# untitled.net
KiCad netlist of a schematic drawn in EAGLE
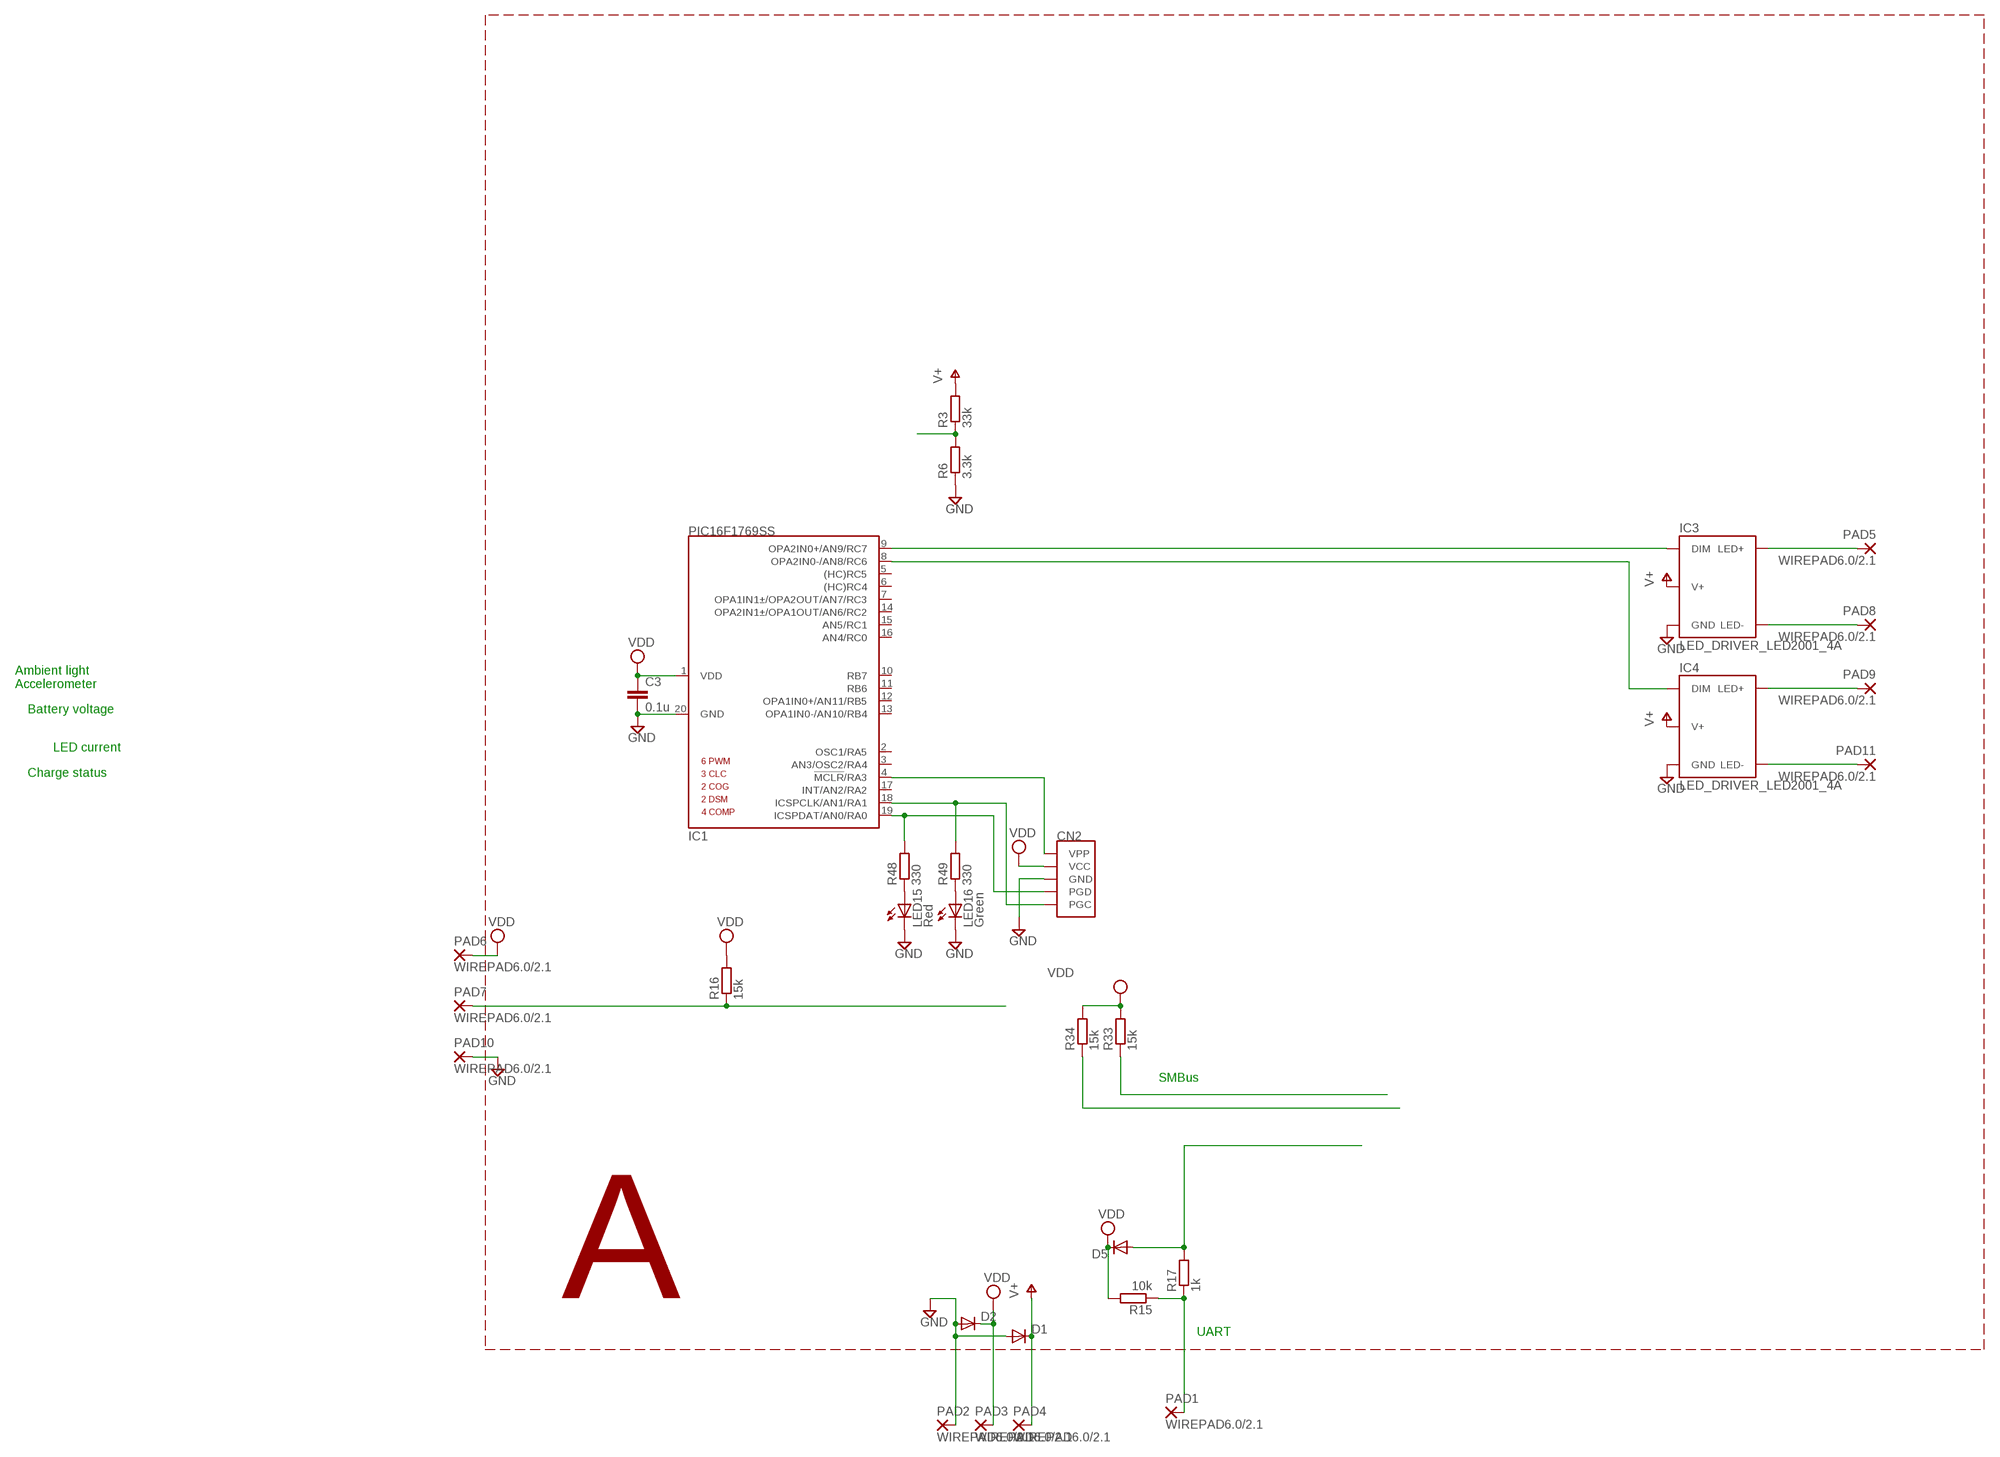
[diagram p0: schematic, sheet 1]

(export (version "E")
  (design (tool "Eeschema 10.0.6"))
  (components
    (comp (ref "C3")
      (value "0.1u")
      (footprint "eagle-import:C0402")
      (libsource (lib "eagle-import") (part "C-EUC0402"))
    )
    (comp (ref "CN2")
      (value "ICSPPIN")
      (footprint "eagle-import:MINI-ICSP_PIN")
      (libsource (lib "eagle-import") (part "ICSPPIN"))
    )
    (comp (ref "D1")
      (value "DIODE-VMN2")
      (footprint "eagle-import:VMN2")
      (libsource (lib "eagle-import") (part "DIODE-VMN2"))
    )
    (comp (ref "D2")
      (value "DIODE-VMN2")
      (footprint "eagle-import:VMN2")
      (libsource (lib "eagle-import") (part "DIODE-VMN2"))
    )
    (comp (ref "D5")
      (value "DIODE-VMN2")
      (footprint "eagle-import:VMN2")
      (libsource (lib "eagle-import") (part "DIODE-VMN2"))
    )
    (comp (ref "IC1")
      (value "PIC16F1769SS")
      (footprint "eagle-import:SSOP20")
      (libsource (lib "eagle-import") (part "PIC16F1769SS"))
    )
    (comp (ref "IC3")
      (value "LED_DRIVER_LED2001_4A")
      (footprint "eagle-import:LED_DRIVER_LED2001_4A")
      (libsource (lib "eagle-import") (part "LED_DRIVER_LED2001_4A"))
    )
    (comp (ref "IC4")
      (value "LED_DRIVER_LED2001_4A")
      (footprint "eagle-import:LED_DRIVER_LED2001_4A")
      (libsource (lib "eagle-import") (part "LED_DRIVER_LED2001_4A"))
    )
    (comp (ref "LED15")
      (value "Red")
      (footprint "eagle-import:LED3MM")
      (libsource (lib "eagle-import") (part "LED3MM"))
    )
    (comp (ref "LED16")
      (value "Green")
      (footprint "eagle-import:LED3MM")
      (libsource (lib "eagle-import") (part "LED3MM"))
    )
    (comp (ref "PAD1")
      (value "WIREPAD6.0/2.1")
      (footprint "eagle-import:6.0_2.1")
      (libsource (lib "eagle-import") (part "WIREPAD6.0/2.1"))
    )
    (comp (ref "PAD2")
      (value "WIREPAD6.0/2.1")
      (footprint "eagle-import:6.0_2.1")
      (libsource (lib "eagle-import") (part "WIREPAD6.0/2.1"))
    )
    (comp (ref "PAD3")
      (value "WIREPAD6.0/2.1")
      (footprint "eagle-import:6.0_2.1")
      (libsource (lib "eagle-import") (part "WIREPAD6.0/2.1"))
    )
    (comp (ref "PAD4")
      (value "WIREPAD6.0/2.1")
      (footprint "eagle-import:6.0_2.1")
      (libsource (lib "eagle-import") (part "WIREPAD6.0/2.1"))
    )
    (comp (ref "PAD5")
      (value "WIREPAD6.0/2.1")
      (footprint "eagle-import:6.0_2.1")
      (libsource (lib "eagle-import") (part "WIREPAD6.0/2.1"))
    )
    (comp (ref "PAD6")
      (value "WIREPAD6.0/2.1")
      (footprint "eagle-import:6.0_2.1")
      (libsource (lib "eagle-import") (part "WIREPAD6.0/2.1"))
    )
    (comp (ref "PAD7")
      (value "WIREPAD6.0/2.1")
      (footprint "eagle-import:6.0_2.1")
      (libsource (lib "eagle-import") (part "WIREPAD6.0/2.1"))
    )
    (comp (ref "PAD8")
      (value "WIREPAD6.0/2.1")
      (footprint "eagle-import:6.0_2.1")
      (libsource (lib "eagle-import") (part "WIREPAD6.0/2.1"))
    )
    (comp (ref "PAD9")
      (value "WIREPAD6.0/2.1")
      (footprint "eagle-import:6.0_2.1")
      (libsource (lib "eagle-import") (part "WIREPAD6.0/2.1"))
    )
    (comp (ref "PAD10")
      (value "WIREPAD6.0/2.1")
      (footprint "eagle-import:6.0_2.1")
      (libsource (lib "eagle-import") (part "WIREPAD6.0/2.1"))
    )
    (comp (ref "PAD11")
      (value "WIREPAD6.0/2.1")
      (footprint "eagle-import:6.0_2.1")
      (libsource (lib "eagle-import") (part "WIREPAD6.0/2.1"))
    )
    (comp (ref "R3")
      (value "33k")
      (footprint "eagle-import:R0402")
      (libsource (lib "eagle-import") (part "R-EU_R0402"))
    )
    (comp (ref "R6")
      (value "3.3k")
      (footprint "eagle-import:R0402")
      (libsource (lib "eagle-import") (part "R-EU_R0402"))
    )
    (comp (ref "R15")
      (value "10k")
      (footprint "eagle-import:R0402")
      (libsource (lib "eagle-import") (part "R-EU_R0402"))
    )
    (comp (ref "R16")
      (value "15k")
      (footprint "eagle-import:R0402")
      (libsource (lib "eagle-import") (part "R-EU_R0402"))
    )
    (comp (ref "R17")
      (value "1k")
      (footprint "eagle-import:R0402")
      (libsource (lib "eagle-import") (part "R-EU_R0402"))
    )
    (comp (ref "R33")
      (value "15k")
      (footprint "eagle-import:R0402")
      (libsource (lib "eagle-import") (part "R-EU_R0402"))
    )
    (comp (ref "R34")
      (value "15k")
      (footprint "eagle-import:R0402")
      (libsource (lib "eagle-import") (part "R-EU_R0402"))
    )
    (comp (ref "R48")
      (value "330")
      (footprint "eagle-import:R0402")
      (libsource (lib "eagle-import") (part "R-EU_R0402"))
    )
    (comp (ref "R49")
      (value "330")
      (footprint "eagle-import:R0402")
      (libsource (lib "eagle-import") (part "R-EU_R0402"))
    )
  )
  (nets
    (net (code "1") (name "GND") (class "Default")
      (node (ref "C3") (pin "2") (pinfunction "2_2") (pintype "passive"))
      (node (ref "CN2") (pin "GND") (pinfunction "GND_GND") (pintype "power_in"))
      (node (ref "D1") (pin "A") (pinfunction "A_A") (pintype "passive"))
      (node (ref "D2") (pin "A") (pinfunction "A_A") (pintype "passive"))
      (node (ref "IC1") (pin "20") (pinfunction "GND_20") (pintype "power_in"))
      (node (ref "IC3") (pin "GND") (pinfunction "GND_GND") (pintype "power_in"))
      (node (ref "IC4") (pin "GND") (pinfunction "GND_GND") (pintype "power_in"))
      (node (ref "LED15") (pin "K") (pinfunction "C_K") (pintype "passive"))
      (node (ref "LED16") (pin "K") (pinfunction "C_K") (pintype "passive"))
      (node (ref "PAD10") (pin "1") (pinfunction "P_1") (pintype "passive"))
      (node (ref "PAD2") (pin "1") (pinfunction "P_1") (pintype "passive"))
      (node (ref "R6") (pin "1") (pinfunction "1_1") (pintype "passive"))
    )
    (net (code "2") (name "Net-(D5-PadA)") (class "Default")
      (node (ref "D5") (pin "A") (pinfunction "A_A") (pintype "passive"))
      (node (ref "R17") (pin "2") (pinfunction "2_2") (pintype "passive"))
    )
    (net (code "3") (name "Net-(IC1-ICSPCLK{slash}AN1{slash}RA1)") (class "Default")
      (node (ref "CN2") (pin "PGC") (pinfunction "PGC_PGC") (pintype "output"))
      (node (ref "IC1") (pin "18") (pinfunction "ICSPCLK/AN1/RA1_18") (pintype "bidirectional"))
      (node (ref "R49") (pin "2") (pinfunction "2_2") (pintype "passive"))
    )
    (net (code "4") (name "Net-(IC1-ICSPDAT{slash}AN0{slash}RA0)") (class "Default")
      (node (ref "CN2") (pin "PGD") (pinfunction "PGD_PGD") (pintype "bidirectional"))
      (node (ref "IC1") (pin "19") (pinfunction "ICSPDAT/AN0/RA0_19") (pintype "bidirectional"))
      (node (ref "R48") (pin "2") (pinfunction "2_2") (pintype "passive"))
    )
    (net (code "5") (name "Net-(IC1-OPA2IN0+{slash}AN9{slash}RC7)") (class "Default")
      (node (ref "IC1") (pin "9") (pinfunction "OPA2IN0+/AN9/RC7_9") (pintype "bidirectional"))
      (node (ref "IC3") (pin "DIM") (pinfunction "DIM_DIM") (pintype "input"))
    )
    (net (code "6") (name "Net-(IC1-OPA2IN0-{slash}AN8{slash}RC6)") (class "Default")
      (node (ref "IC1") (pin "8") (pinfunction "OPA2IN0-/AN8/RC6_8") (pintype "bidirectional"))
      (node (ref "IC4") (pin "DIM") (pinfunction "DIM_DIM") (pintype "input"))
    )
    (net (code "7") (name "Net-(IC1-~{MCLR}{slash}RA3)") (class "Default")
      (node (ref "CN2") (pin "VPP") (pinfunction "VPP_VPP") (pintype "output"))
      (node (ref "IC1") (pin "4") (pinfunction "~{MCLR}/RA3_4") (pintype "input"))
    )
    (net (code "8") (name "Net-(LED15-PadA)") (class "Default")
      (node (ref "LED15") (pin "A") (pinfunction "A_A") (pintype "passive"))
      (node (ref "R48") (pin "1") (pinfunction "1_1") (pintype "passive"))
    )
    (net (code "9") (name "Net-(LED16-PadA)") (class "Default")
      (node (ref "LED16") (pin "A") (pinfunction "A_A") (pintype "passive"))
      (node (ref "R49") (pin "1") (pinfunction "1_1") (pintype "passive"))
    )
    (net (code "10") (name "Net-(PAD1-P)") (class "Default")
      (node (ref "PAD1") (pin "1") (pinfunction "P_1") (pintype "passive"))
      (node (ref "R15") (pin "1") (pinfunction "1_1") (pintype "passive"))
      (node (ref "R17") (pin "1") (pinfunction "1_1") (pintype "passive"))
    )
    (net (code "11") (name "Net-(PAD5-P)") (class "Default")
      (node (ref "IC3") (pin "LED+") (pinfunction "LED+_LED+") (pintype "output"))
      (node (ref "PAD5") (pin "1") (pinfunction "P_1") (pintype "passive"))
    )
    (net (code "12") (name "Net-(PAD7-P)") (class "Default")
      (node (ref "PAD7") (pin "1") (pinfunction "P_1") (pintype "passive"))
      (node (ref "R16") (pin "1") (pinfunction "1_1") (pintype "passive"))
    )
    (net (code "13") (name "Net-(PAD8-P)") (class "Default")
      (node (ref "IC3") (pin "LED-") (pinfunction "LED-_LED-") (pintype "output"))
      (node (ref "PAD8") (pin "1") (pinfunction "P_1") (pintype "passive"))
    )
    (net (code "14") (name "Net-(PAD9-P)") (class "Default")
      (node (ref "IC4") (pin "LED+") (pinfunction "LED+_LED+") (pintype "output"))
      (node (ref "PAD9") (pin "1") (pinfunction "P_1") (pintype "passive"))
    )
    (net (code "15") (name "Net-(PAD11-P)") (class "Default")
      (node (ref "IC4") (pin "LED-") (pinfunction "LED-_LED-") (pintype "output"))
      (node (ref "PAD11") (pin "1") (pinfunction "P_1") (pintype "passive"))
    )
    (net (code "16") (name "Net-(R3-Pad1)") (class "Default")
      (node (ref "R3") (pin "1") (pinfunction "1_1") (pintype "passive"))
      (node (ref "R6") (pin "2") (pinfunction "2_2") (pintype "passive"))
    )
    (net (code "17") (name "V+") (class "Default")
      (node (ref "D1") (pin "C") (pinfunction "C_C") (pintype "passive"))
      (node (ref "IC3") (pin "V+") (pinfunction "V+_V+") (pintype "power_in"))
      (node (ref "IC4") (pin "V+") (pinfunction "V+_V+") (pintype "power_in"))
      (node (ref "PAD4") (pin "1") (pinfunction "P_1") (pintype "passive"))
      (node (ref "R3") (pin "2") (pinfunction "2_2") (pintype "passive"))
    )
    (net (code "18") (name "VDD") (class "Default")
      (node (ref "C3") (pin "1") (pinfunction "1_1") (pintype "passive"))
      (node (ref "CN2") (pin "VCC") (pinfunction "VCC_VCC") (pintype "power_in"))
      (node (ref "D2") (pin "C") (pinfunction "C_C") (pintype "passive"))
      (node (ref "D5") (pin "C") (pinfunction "C_C") (pintype "passive"))
      (node (ref "IC1") (pin "1") (pinfunction "VDD_1") (pintype "power_in"))
      (node (ref "PAD3") (pin "1") (pinfunction "P_1") (pintype "passive"))
      (node (ref "PAD6") (pin "1") (pinfunction "P_1") (pintype "passive"))
      (node (ref "R15") (pin "2") (pinfunction "2_2") (pintype "passive"))
      (node (ref "R16") (pin "2") (pinfunction "2_2") (pintype "passive"))
      (node (ref "R33") (pin "2") (pinfunction "2_2") (pintype "passive"))
      (node (ref "R34") (pin "2") (pinfunction "2_2") (pintype "passive"))
    )
    (net (code "19") (name "unconnected-(IC1-(HC)RC4-Pad6)") (class "Default")
      (node (ref "IC1") (pin "6") (pinfunction "(HC)RC4_6") (pintype "bidirectional"))
    )
    (net (code "20") (name "unconnected-(IC1-(HC)RC5-Pad5)") (class "Default")
      (node (ref "IC1") (pin "5") (pinfunction "(HC)RC5_5") (pintype "bidirectional"))
    )
    (net (code "21") (name "unconnected-(IC1-AN3{slash}OSC2{slash}RA4-Pad3)") (class "Default")
      (node (ref "IC1") (pin "3") (pinfunction "AN3/OSC2/RA4_3") (pintype "bidirectional"))
    )
    (net (code "22") (name "unconnected-(IC1-AN4{slash}RC0-Pad16)") (class "Default")
      (node (ref "IC1") (pin "16") (pinfunction "AN4/RC0_16") (pintype "bidirectional"))
    )
    (net (code "23") (name "unconnected-(IC1-AN5{slash}RC1-Pad15)") (class "Default")
      (node (ref "IC1") (pin "15") (pinfunction "AN5/RC1_15") (pintype "bidirectional"))
    )
    (net (code "24") (name "unconnected-(IC1-INT{slash}AN2{slash}RA2-Pad17)") (class "Default")
      (node (ref "IC1") (pin "17") (pinfunction "INT/AN2/RA2_17") (pintype "bidirectional"))
    )
    (net (code "25") (name "unconnected-(IC1-OPA1IN0+{slash}AN11{slash}RB5-Pad12)") (class "Default")
      (node (ref "IC1") (pin "12") (pinfunction "OPA1IN0+/AN11/RB5_12") (pintype "bidirectional"))
    )
    (net (code "26") (name "unconnected-(IC1-OPA1IN0-{slash}AN10{slash}RB4-Pad13)") (class "Default")
      (node (ref "IC1") (pin "13") (pinfunction "OPA1IN0-/AN10/RB4_13") (pintype "bidirectional"))
    )
    (net (code "27") (name "unconnected-(IC1-OPA1IN1±{slash}OPA2OUT{slash}AN7{slash}RC3-Pad7)") (class "Default")
      (node (ref "IC1") (pin "7") (pinfunction "OPA1IN1±/OPA2OUT/AN7/RC3_7") (pintype "bidirectional"))
    )
    (net (code "28") (name "unconnected-(IC1-OPA2IN1±{slash}OPA1OUT{slash}AN6{slash}RC2-Pad14)") (class "Default")
      (node (ref "IC1") (pin "14") (pinfunction "OPA2IN1±/OPA1OUT/AN6/RC2_14") (pintype "bidirectional"))
    )
    (net (code "29") (name "unconnected-(IC1-OSC1{slash}RA5-Pad2)") (class "Default")
      (node (ref "IC1") (pin "2") (pinfunction "OSC1/RA5_2") (pintype "bidirectional"))
    )
    (net (code "30") (name "unconnected-(IC1-RB6-Pad11)") (class "Default")
      (node (ref "IC1") (pin "11") (pinfunction "RB6_11") (pintype "bidirectional"))
    )
    (net (code "31") (name "unconnected-(IC1-RB7-Pad10)") (class "Default")
      (node (ref "IC1") (pin "10") (pinfunction "RB7_10") (pintype "bidirectional"))
    )
    (net (code "32") (name "unconnected-(R33-Pad1)") (class "Default")
      (node (ref "R33") (pin "1") (pinfunction "1_1") (pintype "passive"))
    )
    (net (code "33") (name "unconnected-(R34-Pad1)") (class "Default")
      (node (ref "R34") (pin "1") (pinfunction "1_1") (pintype "passive"))
    )
  )
)
